# NanjaTown02.net
KiCad netlist of a schematic drawn in EAGLE
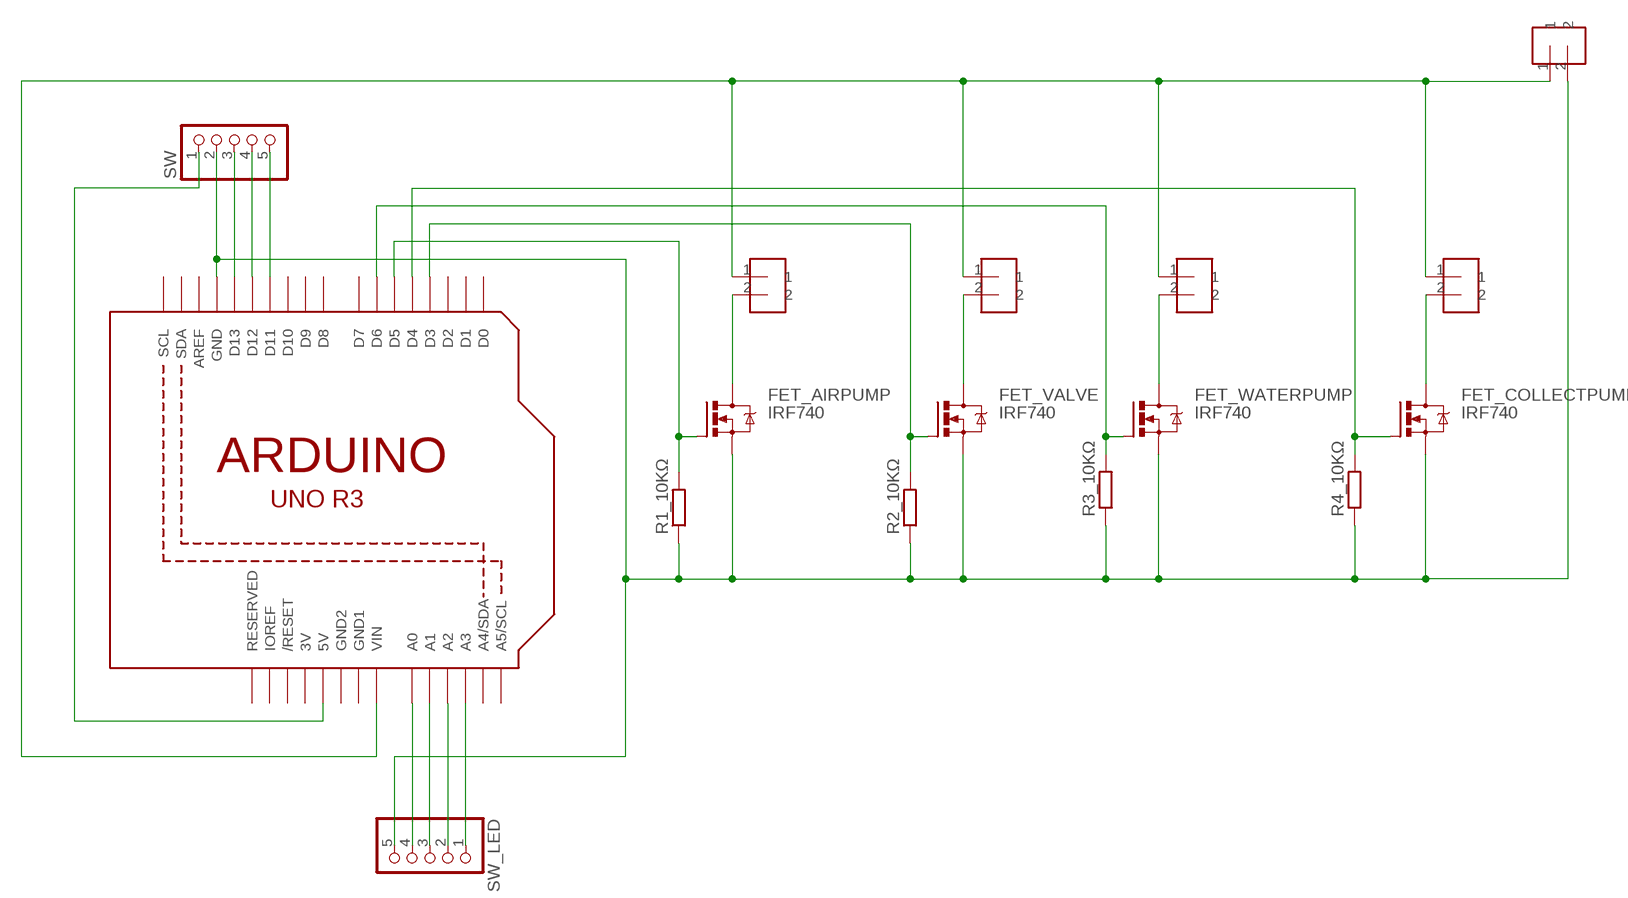
[diagram p0: schematic, sheet 1]

(export (version "E")
  (design (tool "Eeschema 10.0.6"))
  (components
    (comp (ref "FET_AIRPUMP")
      (value "IRF740")
      (footprint "eagle-import:TO220BV")
      (libsource (lib "eagle-import") (part "IRF740"))
    )
    (comp (ref "FET_COLLECTPUMP")
      (value "IRF740")
      (footprint "eagle-import:TO220BV")
      (libsource (lib "eagle-import") (part "IRF740"))
    )
    (comp (ref "FET_VALVE")
      (value "IRF740")
      (footprint "eagle-import:TO220BV")
      (libsource (lib "eagle-import") (part "IRF740"))
    )
    (comp (ref "FET_WATERPUMP")
      (value "IRF740")
      (footprint "eagle-import:TO220BV")
      (libsource (lib "eagle-import") (part "IRF740"))
    )
    (comp (ref "R1_10KΩ")
      (value "R-EU_0207/10")
      (footprint "eagle-import:0207_10")
      (libsource (lib "eagle-import") (part "R-EU_0207/10"))
    )
    (comp (ref "R2_10KΩ")
      (value "R-EU_0207/10")
      (footprint "eagle-import:0207_10")
      (libsource (lib "eagle-import") (part "R-EU_0207/10"))
    )
    (comp (ref "R3_10KΩ")
      (value "R-EU_0207/10")
      (footprint "eagle-import:0207_10")
      (libsource (lib "eagle-import") (part "R-EU_0207/10"))
    )
    (comp (ref "R4_10KΩ")
      (value "R-EU_0207/10")
      (footprint "eagle-import:0207_10")
      (libsource (lib "eagle-import") (part "R-EU_0207/10"))
    )
    (comp (ref "SW")
      (value "PINHD-1X5")
      (footprint "eagle-import:1X05")
      (libsource (lib "eagle-import") (part "PINHD-1X5"))
    )
    (comp (ref "SW_LED")
      (value "PINHD-1X5/90")
      (footprint "eagle-import:1X05_90")
      (libsource (lib "eagle-import") (part "PINHD-1X5/90"))
    )
    (comp (ref "TERMINAL_AIRPUMP")
      (value "TERMINAL_BLOCK_5.08MM")
      (footprint "eagle-import:TERMINAL_BLOCK_5.8MM")
      (libsource (lib "eagle-import") (part "TERMINAL_BLOCK_5.08MM"))
    )
    (comp (ref "TERMINAL_COLLECTPUMP")
      (value "TERMINAL_BLOCK_5.08MM")
      (footprint "eagle-import:TERMINAL_BLOCK_5.8MM")
      (libsource (lib "eagle-import") (part "TERMINAL_BLOCK_5.08MM"))
    )
    (comp (ref "TERMINAL_VALVE")
      (value "TERMINAL_BLOCK_5.08MM")
      (footprint "eagle-import:TERMINAL_BLOCK_5.8MM")
      (libsource (lib "eagle-import") (part "TERMINAL_BLOCK_5.08MM"))
    )
    (comp (ref "TERMINAL_WATERPUMP")
      (value "TERMINAL_BLOCK_5.08MM")
      (footprint "eagle-import:TERMINAL_BLOCK_5.8MM")
      (libsource (lib "eagle-import") (part "TERMINAL_BLOCK_5.08MM"))
    )
    (comp (ref "U$1")
      (value "TERMINAL_BLOCK_5.08MM")
      (footprint "eagle-import:TERMINAL_BLOCK_5.8MM")
      (libsource (lib "eagle-import") (part "TERMINAL_BLOCK_5.08MM"))
    )
    (comp (ref "U1")
      (value "ARDUINOR3-DIMENSION")
      (footprint "eagle-import:ARDUINOR3")
      (libsource (lib "eagle-import") (part "ARDUINOR3-DIMENSION"))
    )
  )
  (nets
    (net (code "1") (name "/3V") (class "Default")
      (node (ref "U1") (pin "3V") (pinfunction "3V_3V") (pintype "power_in"))
    )
    (net (code "2") (name "/GND1") (class "Default")
      (node (ref "U1") (pin "GND1") (pinfunction "GND1_GND1") (pintype "power_in"))
    )
    (net (code "3") (name "/GND2") (class "Default")
      (node (ref "U1") (pin "GND2") (pinfunction "GND2_GND2") (pintype "power_in"))
    )
    (net (code "4") (name "Net-(FET_AIRPUMP-PadD)") (class "Default")
      (node (ref "FET_AIRPUMP") (pin "D") (pinfunction "D_D") (pintype "passive"))
      (node (ref "TERMINAL_AIRPUMP") (pin "2") (pinfunction "2_2") (pintype "bidirectional"))
    )
    (net (code "5") (name "Net-(FET_AIRPUMP-PadG)") (class "Default")
      (node (ref "FET_AIRPUMP") (pin "G") (pinfunction "G_G") (pintype "passive"))
      (node (ref "R1_10KΩ") (pin "2") (pinfunction "2_2") (pintype "passive"))
      (node (ref "U1") (pin "D5") (pinfunction "D5_D5") (pintype "bidirectional"))
    )
    (net (code "6") (name "Net-(FET_AIRPUMP-PadS)") (class "Default")
      (node (ref "FET_AIRPUMP") (pin "S") (pinfunction "S_S") (pintype "passive"))
      (node (ref "FET_COLLECTPUMP") (pin "S") (pinfunction "S_S") (pintype "passive"))
      (node (ref "FET_VALVE") (pin "S") (pinfunction "S_S") (pintype "passive"))
      (node (ref "FET_WATERPUMP") (pin "S") (pinfunction "S_S") (pintype "passive"))
      (node (ref "R1_10KΩ") (pin "1") (pinfunction "1_1") (pintype "passive"))
      (node (ref "R2_10KΩ") (pin "1") (pinfunction "1_1") (pintype "passive"))
      (node (ref "R3_10KΩ") (pin "1") (pinfunction "1_1") (pintype "passive"))
      (node (ref "R4_10KΩ") (pin "1") (pinfunction "1_1") (pintype "passive"))
      (node (ref "SW") (pin "2") (pinfunction "2_2") (pintype "passive"))
      (node (ref "SW_LED") (pin "5") (pinfunction "5_5") (pintype "passive"))
      (node (ref "U$1") (pin "2") (pinfunction "2_2") (pintype "bidirectional"))
      (node (ref "U1") (pin "GND") (pinfunction "GND_GND") (pintype "power_in"))
    )
    (net (code "7") (name "Net-(FET_COLLECTPUMP-PadD)") (class "Default")
      (node (ref "FET_COLLECTPUMP") (pin "D") (pinfunction "D_D") (pintype "passive"))
      (node (ref "TERMINAL_COLLECTPUMP") (pin "2") (pinfunction "2_2") (pintype "bidirectional"))
    )
    (net (code "8") (name "Net-(FET_COLLECTPUMP-PadG)") (class "Default")
      (node (ref "FET_COLLECTPUMP") (pin "G") (pinfunction "G_G") (pintype "passive"))
      (node (ref "R4_10KΩ") (pin "2") (pinfunction "2_2") (pintype "passive"))
      (node (ref "U1") (pin "D4") (pinfunction "D4_D4") (pintype "bidirectional"))
    )
    (net (code "9") (name "Net-(FET_VALVE-PadD)") (class "Default")
      (node (ref "FET_VALVE") (pin "D") (pinfunction "D_D") (pintype "passive"))
      (node (ref "TERMINAL_VALVE") (pin "2") (pinfunction "2_2") (pintype "bidirectional"))
    )
    (net (code "10") (name "Net-(FET_VALVE-PadG)") (class "Default")
      (node (ref "FET_VALVE") (pin "G") (pinfunction "G_G") (pintype "passive"))
      (node (ref "R2_10KΩ") (pin "2") (pinfunction "2_2") (pintype "passive"))
      (node (ref "U1") (pin "D3") (pinfunction "D3_D3") (pintype "bidirectional"))
    )
    (net (code "11") (name "Net-(FET_WATERPUMP-PadD)") (class "Default")
      (node (ref "FET_WATERPUMP") (pin "D") (pinfunction "D_D") (pintype "passive"))
      (node (ref "TERMINAL_WATERPUMP") (pin "2") (pinfunction "2_2") (pintype "bidirectional"))
    )
    (net (code "12") (name "Net-(FET_WATERPUMP-PadG)") (class "Default")
      (node (ref "FET_WATERPUMP") (pin "G") (pinfunction "G_G") (pintype "passive"))
      (node (ref "R3_10KΩ") (pin "2") (pinfunction "2_2") (pintype "passive"))
      (node (ref "U1") (pin "D6") (pinfunction "D6_D6") (pintype "bidirectional"))
    )
    (net (code "13") (name "Net-(SW-Pad1)") (class "Default")
      (node (ref "SW") (pin "1") (pinfunction "1_1") (pintype "passive"))
      (node (ref "U1") (pin "5V") (pinfunction "5V_5V") (pintype "power_in"))
    )
    (net (code "14") (name "Net-(SW-Pad3)") (class "Default")
      (node (ref "SW") (pin "3") (pinfunction "3_3") (pintype "passive"))
      (node (ref "U1") (pin "D13") (pinfunction "D13_D13") (pintype "bidirectional"))
    )
    (net (code "15") (name "Net-(SW-Pad4)") (class "Default")
      (node (ref "SW") (pin "4") (pinfunction "4_4") (pintype "passive"))
      (node (ref "U1") (pin "D12") (pinfunction "D12_D12") (pintype "bidirectional"))
    )
    (net (code "16") (name "Net-(SW-Pad5)") (class "Default")
      (node (ref "SW") (pin "5") (pinfunction "5_5") (pintype "passive"))
      (node (ref "U1") (pin "D11") (pinfunction "D11_D11") (pintype "bidirectional"))
    )
    (net (code "17") (name "Net-(SW_LED-Pad1)") (class "Default")
      (node (ref "SW_LED") (pin "1") (pinfunction "1_1") (pintype "passive"))
      (node (ref "U1") (pin "A3") (pinfunction "A3_A3") (pintype "bidirectional"))
    )
    (net (code "18") (name "Net-(SW_LED-Pad2)") (class "Default")
      (node (ref "SW_LED") (pin "2") (pinfunction "2_2") (pintype "passive"))
      (node (ref "U1") (pin "A2") (pinfunction "A2_A2") (pintype "bidirectional"))
    )
    (net (code "19") (name "Net-(SW_LED-Pad3)") (class "Default")
      (node (ref "SW_LED") (pin "3") (pinfunction "3_3") (pintype "passive"))
      (node (ref "U1") (pin "A1") (pinfunction "A1_A1") (pintype "bidirectional"))
    )
    (net (code "20") (name "Net-(SW_LED-Pad4)") (class "Default")
      (node (ref "SW_LED") (pin "4") (pinfunction "4_4") (pintype "passive"))
      (node (ref "U1") (pin "A0") (pinfunction "A0_A0") (pintype "bidirectional"))
    )
    (net (code "21") (name "Net-(TERMINAL_AIRPUMP-Pad1)") (class "Default")
      (node (ref "TERMINAL_AIRPUMP") (pin "1") (pinfunction "1_1") (pintype "bidirectional"))
      (node (ref "TERMINAL_COLLECTPUMP") (pin "1") (pinfunction "1_1") (pintype "bidirectional"))
      (node (ref "TERMINAL_VALVE") (pin "1") (pinfunction "1_1") (pintype "bidirectional"))
      (node (ref "TERMINAL_WATERPUMP") (pin "1") (pinfunction "1_1") (pintype "bidirectional"))
      (node (ref "U$1") (pin "1") (pinfunction "1_1") (pintype "bidirectional"))
      (node (ref "U1") (pin "VIN") (pinfunction "VIN_VIN") (pintype "power_in"))
    )
    (net (code "22") (name "unconnected-(U1-A4{slash}SDA-PadA4)") (class "Default")
      (node (ref "U1") (pin "A4") (pinfunction "A4/SDA_A4") (pintype "bidirectional"))
    )
    (net (code "23") (name "unconnected-(U1-A5{slash}SCL-PadA5)") (class "Default")
      (node (ref "U1") (pin "A5") (pinfunction "A5/SCL_A5") (pintype "bidirectional"))
    )
    (net (code "24") (name "unconnected-(U1-PadAREF)") (class "Default")
      (node (ref "U1") (pin "AREF") (pinfunction "AREF_AREF") (pintype "bidirectional"))
    )
    (net (code "25") (name "unconnected-(U1-PadD0)") (class "Default")
      (node (ref "U1") (pin "D0") (pinfunction "D0_D0") (pintype "bidirectional"))
    )
    (net (code "26") (name "unconnected-(U1-PadD1)") (class "Default")
      (node (ref "U1") (pin "D1") (pinfunction "D1_D1") (pintype "bidirectional"))
    )
    (net (code "27") (name "unconnected-(U1-PadD2)") (class "Default")
      (node (ref "U1") (pin "D2") (pinfunction "D2_D2") (pintype "bidirectional"))
    )
    (net (code "28") (name "unconnected-(U1-PadD7)") (class "Default")
      (node (ref "U1") (pin "D7") (pinfunction "D7_D7") (pintype "bidirectional"))
    )
    (net (code "29") (name "unconnected-(U1-PadD8)") (class "Default")
      (node (ref "U1") (pin "D8") (pinfunction "D8_D8") (pintype "bidirectional"))
    )
    (net (code "30") (name "unconnected-(U1-PadD9)") (class "Default")
      (node (ref "U1") (pin "D9") (pinfunction "D9_D9") (pintype "bidirectional"))
    )
    (net (code "31") (name "unconnected-(U1-PadD10)") (class "Default")
      (node (ref "U1") (pin "D10") (pinfunction "D10_D10") (pintype "bidirectional"))
    )
    (net (code "32") (name "unconnected-(U1-PadIOREF)") (class "Default")
      (node (ref "U1") (pin "IOREF") (pinfunction "IOREF_IOREF") (pintype "output"))
    )
    (net (code "33") (name "unconnected-(U1-PadRESERVED)") (class "Default")
      (node (ref "U1") (pin "RESERVED") (pinfunction "RESERVED_RESERVED") (pintype "no_connect"))
    )
    (net (code "34") (name "unconnected-(U1-PadSCL)") (class "Default")
      (node (ref "U1") (pin "SCL") (pinfunction "SCL_SCL") (pintype "bidirectional"))
    )
    (net (code "35") (name "unconnected-(U1-PadSDA)") (class "Default")
      (node (ref "U1") (pin "SDA") (pinfunction "SDA_SDA") (pintype "bidirectional"))
    )
    (net (code "36") (name "unconnected-(U1-{slash}RESET-PadRESET)") (class "Default")
      (node (ref "U1") (pin "RESET") (pinfunction "/RESET_RESET") (pintype "bidirectional"))
    )
  )
)
